# TI_FREQ.net
KiCad netlist of a schematic drawn in Altium Designer
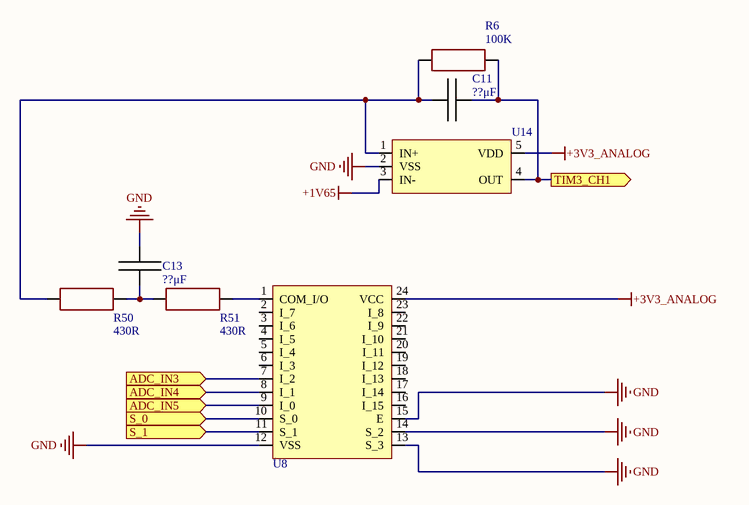
[diagram p0: TI_FREQ.SchDoc]

(export (version "E")
  (design (tool "Eeschema 10.0.6"))
  (components
    (comp (ref "C11")
      (value "??μF")
      (footprint "CAP: 0603")
      (fields (field (name "VOLTAGE") "??V") (field (name "Comment") "Cap_0603"))
      (libsource (lib "capacitor") (part "Cap_0603"))
    )
    (comp (ref "C13")
      (value "??μF")
      (footprint "CAP: 0603")
      (fields (field (name "VOLTAGE") "??V") (field (name "Comment") "Cap_0603"))
      (libsource (lib "capacitor") (part "Cap_0603"))
    )
    (comp (ref "R6")
      (value "100K")
      (footprint "RES: 0603")
      (fields
        (field (name "POWER") "0.1W")
        (field (name "TOLERANCE") "±5%")
        (field (name "Comment") "Resistor_0603")
      )
      (libsource (lib "") (part "Resistor_0603_1"))
    )
    (comp (ref "R50")
      (value "430R")
      (footprint "RES: 0603")
      (fields
        (field (name "POWER") "0.1W")
        (field (name "TOLERANCE") "±5%")
        (field (name "Comment") "Resistor_0603")
      )
      (libsource (lib "resistor") (part "Resistor_0603"))
    )
    (comp (ref "R51")
      (value "430R")
      (footprint "RES: 0603")
      (fields
        (field (name "POWER") "0.1W")
        (field (name "TOLERANCE") "±5%")
        (field (name "Comment") "Resistor_0603")
      )
      (libsource (lib "resistor") (part "Resistor_0603"))
    )
    (comp (ref "U8")
      (value "CD74HC4067M96")
      (footprint "SOIC-24")
      (description "1 MHz, Low-Power Op Amp")
      (fields (field (name "MANUFACTURER") "Texas Instruments"))
      (libsource (lib "MY_INT_LIB") (part "CD74HC4067M96"))
    )
    (comp (ref "U14")
      (value "MCP6001U")
      (footprint "SOT-23-5")
      (description "1 MHz, Low-Power Op Amp")
      (fields (field (name "MANUFACTURER") "Microchip"))
      (libsource (lib "MY_INT_LIB") (part "MCP6001U"))
    )
  )
  (nets
    (net (code "1") (name "+1V65") (class "Default")
      (node (ref "U14") (pin "3") (pinfunction "IN-_3") (pintype "passive"))
    )
    (net (code "2") (name "+3V3_ANALOG") (class "Default")
      (node (ref "U14") (pin "5") (pinfunction "VDD_5") (pintype "power_in"))
      (node (ref "U8") (pin "24") (pinfunction "VCC_24") (pintype "power_in"))
    )
    (net (code "3") (name "/ADC_IN3") (class "Default")
      (node (ref "U8") (pin "7") (pinfunction "I_2_7") (pintype "passive"))
    )
    (net (code "4") (name "/ADC_IN4") (class "Default")
      (node (ref "U8") (pin "8") (pinfunction "I_1_8") (pintype "passive"))
    )
    (net (code "5") (name "/ADC_IN5") (class "Default")
      (node (ref "U8") (pin "9") (pinfunction "I_0_9") (pintype "passive"))
    )
    (net (code "6") (name "/S_0") (class "Default")
      (node (ref "U8") (pin "10") (pinfunction "S_0_10") (pintype "passive"))
    )
    (net (code "7") (name "/S_1") (class "Default")
      (node (ref "U8") (pin "11") (pinfunction "S_1_11") (pintype "passive"))
    )
    (net (code "8") (name "/TIM3_CH1") (class "Default")
      (node (ref "C11") (pin "2") (pinfunction "2_2") (pintype "passive"))
      (node (ref "R6") (pin "1") (pinfunction "1_1") (pintype "passive"))
      (node (ref "U14") (pin "4") (pinfunction "OUT_4") (pintype "passive"))
    )
    (net (code "9") (name "GND") (class "Default")
      (node (ref "C13") (pin "2") (pinfunction "2_2") (pintype "passive"))
      (node (ref "U14") (pin "2") (pinfunction "VSS_2") (pintype "power_in"))
      (node (ref "U8") (pin "12") (pinfunction "VSS_12") (pintype "power_in"))
      (node (ref "U8") (pin "13") (pinfunction "S_3_13") (pintype "passive"))
      (node (ref "U8") (pin "14") (pinfunction "S_2_14") (pintype "passive"))
      (node (ref "U8") (pin "15") (pinfunction "E_15") (pintype "passive"))
    )
    (net (code "10") (name "Net-(C13-Pad1)") (class "Default")
      (node (ref "C13") (pin "1") (pinfunction "1_1") (pintype "passive"))
      (node (ref "R50") (pin "2") (pinfunction "2_2") (pintype "passive"))
      (node (ref "R51") (pin "1") (pinfunction "1_1") (pintype "passive"))
    )
    (net (code "11") (name "Net-(U8-COM_I{slash}O)") (class "Default")
      (node (ref "R51") (pin "2") (pinfunction "2_2") (pintype "passive"))
      (node (ref "U8") (pin "1") (pinfunction "COM_I/O_1") (pintype "passive"))
    )
    (net (code "12") (name "Net-(U14-IN+)") (class "Default")
      (node (ref "C11") (pin "1") (pinfunction "1_1") (pintype "passive"))
      (node (ref "R50") (pin "1") (pinfunction "1_1") (pintype "passive"))
      (node (ref "R6") (pin "2") (pinfunction "2_2") (pintype "passive"))
      (node (ref "U14") (pin "1") (pinfunction "IN+_1") (pintype "passive"))
    )
    (net (code "13") (name "unconnected-(U8-I_3-Pad6)") (class "Default")
      (node (ref "U8") (pin "6") (pinfunction "I_3_6") (pintype "passive"))
    )
    (net (code "14") (name "unconnected-(U8-I_4-Pad5)") (class "Default")
      (node (ref "U8") (pin "5") (pinfunction "I_4_5") (pintype "passive"))
    )
    (net (code "15") (name "unconnected-(U8-I_5-Pad4)") (class "Default")
      (node (ref "U8") (pin "4") (pinfunction "I_5_4") (pintype "passive"))
    )
    (net (code "16") (name "unconnected-(U8-I_6-Pad3)") (class "Default")
      (node (ref "U8") (pin "3") (pinfunction "I_6_3") (pintype "passive"))
    )
    (net (code "17") (name "unconnected-(U8-I_7-Pad2)") (class "Default")
      (node (ref "U8") (pin "2") (pinfunction "I_7_2") (pintype "passive"))
    )
    (net (code "18") (name "unconnected-(U8-I_8-Pad23)") (class "Default")
      (node (ref "U8") (pin "23") (pinfunction "I_8_23") (pintype "passive"))
    )
    (net (code "19") (name "unconnected-(U8-I_9-Pad22)") (class "Default")
      (node (ref "U8") (pin "22") (pinfunction "I_9_22") (pintype "passive"))
    )
    (net (code "20") (name "unconnected-(U8-I_10-Pad21)") (class "Default")
      (node (ref "U8") (pin "21") (pinfunction "I_10_21") (pintype "passive"))
    )
    (net (code "21") (name "unconnected-(U8-I_11-Pad20)") (class "Default")
      (node (ref "U8") (pin "20") (pinfunction "I_11_20") (pintype "passive"))
    )
    (net (code "22") (name "unconnected-(U8-I_12-Pad19)") (class "Default")
      (node (ref "U8") (pin "19") (pinfunction "I_12_19") (pintype "passive"))
    )
    (net (code "23") (name "unconnected-(U8-I_13-Pad18)") (class "Default")
      (node (ref "U8") (pin "18") (pinfunction "I_13_18") (pintype "passive"))
    )
    (net (code "24") (name "unconnected-(U8-I_14-Pad17)") (class "Default")
      (node (ref "U8") (pin "17") (pinfunction "I_14_17") (pintype "passive"))
    )
    (net (code "25") (name "unconnected-(U8-I_15-Pad16)") (class "Default")
      (node (ref "U8") (pin "16") (pinfunction "I_15_16") (pintype "passive"))
    )
  )
)
